# 555.net
KiCad netlist of a schematic drawn in EAGLE
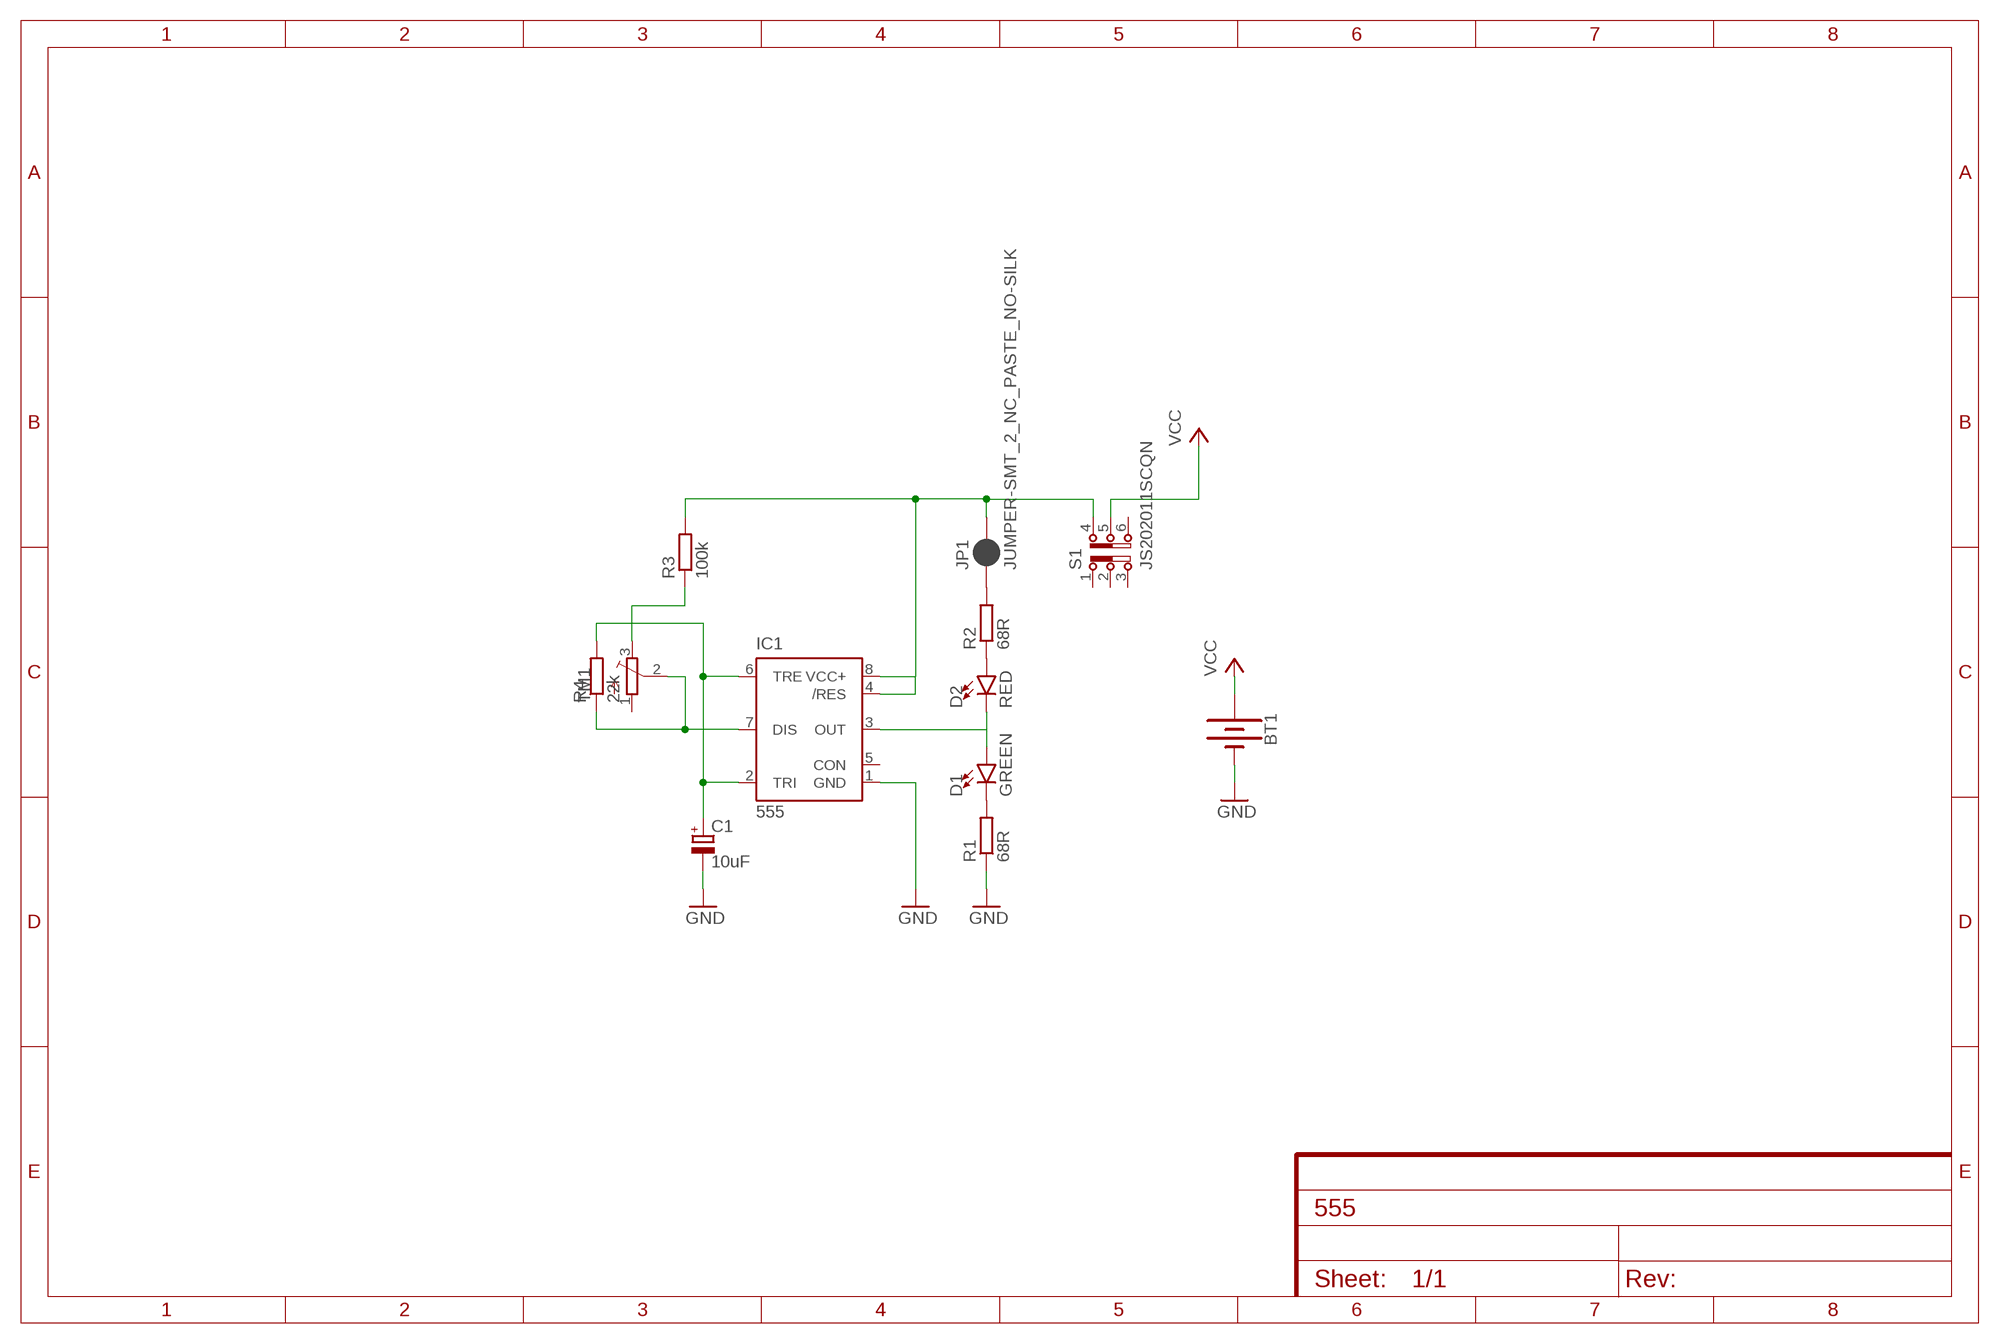
[diagram p0: schematic, sheet 1]

(export (version "E")
  (design (tool "Eeschema 10.0.6"))
  (components
    (comp (ref "BT1")
      (value "BATTERY-20MM_SMD")
      (footprint "eagle-import:BATTCON_20MM")
      (libsource (lib "eagle-import") (part "BATTERY-20MM_SMD"))
    )
    (comp (ref "C1")
      (value "10uF")
      (footprint "eagle-import:SMC_A")
      (libsource (lib "eagle-import") (part "CPOL-EUSMCA"))
    )
    (comp (ref "D1")
      (value "GREEN")
      (footprint "eagle-import:LED-1206")
      (libsource (lib "eagle-import") (part "LED-GREEN1206"))
    )
    (comp (ref "D2")
      (value "RED")
      (footprint "eagle-import:LED-1206")
      (libsource (lib "eagle-import") (part "LED1206"))
    )
    (comp (ref "IC1")
      (value "555")
      (footprint "eagle-import:SO08")
      (libsource (lib "eagle-import") (part "555D"))
    )
    (comp (ref "JP1")
      (value "JUMPER-SMT_2_NC_PASTE_NO-SILK")
      (footprint "eagle-import:SMT-JUMPER_2_NC_PASTE_NO-SILK")
      (libsource (lib "eagle-import") (part "JUMPER-SMT_2_NC_PASTE_NO-SILK"))
    )
    (comp (ref "R1")
      (value "68R")
      (footprint "eagle-import:R0603")
      (libsource (lib "eagle-import") (part "R-EU_R0603"))
    )
    (comp (ref "R2")
      (value "68R")
      (footprint "eagle-import:R0603")
      (libsource (lib "eagle-import") (part "R-EU_R0603"))
    )
    (comp (ref "R3")
      (value "100k")
      (footprint "eagle-import:R0603")
      (libsource (lib "eagle-import") (part "R-EU_R0603"))
    )
    (comp (ref "R4")
      (value "22k")
      (footprint "eagle-import:R0603")
      (libsource (lib "eagle-import") (part "R-EU_R0603"))
    )
    (comp (ref "S1")
      (value "JS202011SCQN")
      (footprint "eagle-import:JS202011SCQN")
      (libsource (lib "eagle-import") (part "JS202011SCQN"))
    )
    (comp (ref "TM1")
      (value "TRIMPOTTC33X")
      (footprint "eagle-import:TC33X")
      (libsource (lib "eagle-import") (part "TRIMPOTTC33X"))
    )
  )
  (nets
    (net (code "1") (name "GND") (class "Default")
      (node (ref "BT1") (pin "2") (pinfunction "-_2") (pintype "power_in"))
      (node (ref "C1") (pin "-") (pinfunction "-_-") (pintype "passive"))
      (node (ref "IC1") (pin "1") (pinfunction "GND_1") (pintype "power_in"))
      (node (ref "R1") (pin "1") (pinfunction "1_1") (pintype "passive"))
    )
    (net (code "2") (name "Net-(D1-PadC)") (class "Default")
      (node (ref "D1") (pin "C") (pinfunction "C_C") (pintype "passive"))
      (node (ref "R1") (pin "2") (pinfunction "2_2") (pintype "passive"))
    )
    (net (code "3") (name "Net-(D2-PadA)") (class "Default")
      (node (ref "D2") (pin "A") (pinfunction "A_A") (pintype "passive"))
      (node (ref "R2") (pin "1") (pinfunction "1_1") (pintype "passive"))
    )
    (net (code "4") (name "Net-(IC1-DIS)") (class "Default")
      (node (ref "IC1") (pin "7") (pinfunction "DIS_7") (pintype "input"))
      (node (ref "R4") (pin "1") (pinfunction "1_1") (pintype "passive"))
      (node (ref "TM1") (pin "2") (pinfunction "S_2") (pintype "passive"))
    )
    (net (code "5") (name "Net-(IC1-OUT)") (class "Default")
      (node (ref "D1") (pin "A") (pinfunction "A_A") (pintype "passive"))
      (node (ref "D2") (pin "C") (pinfunction "C_C") (pintype "passive"))
      (node (ref "IC1") (pin "3") (pinfunction "OUT_3") (pintype "output"))
    )
    (net (code "6") (name "Net-(IC1-TRE)") (class "Default")
      (node (ref "C1") (pin "+") (pinfunction "+_+") (pintype "passive"))
      (node (ref "IC1") (pin "2") (pinfunction "TRI_2") (pintype "input"))
      (node (ref "IC1") (pin "6") (pinfunction "TRE_6") (pintype "input"))
      (node (ref "R4") (pin "2") (pinfunction "2_2") (pintype "passive"))
    )
    (net (code "7") (name "Net-(IC1-VCC+)") (class "Default")
      (node (ref "IC1") (pin "4") (pinfunction "/RES_4") (pintype "input"))
      (node (ref "IC1") (pin "8") (pinfunction "VCC+_8") (pintype "power_in"))
      (node (ref "JP1") (pin "2") (pinfunction "2_2") (pintype "passive"))
      (node (ref "R3") (pin "2") (pinfunction "2_2") (pintype "passive"))
      (node (ref "S1") (pin "4") (pinfunction "4_4") (pintype "passive"))
    )
    (net (code "8") (name "Net-(JP1-Pad1)") (class "Default")
      (node (ref "JP1") (pin "1") (pinfunction "1_1") (pintype "passive"))
      (node (ref "R2") (pin "2") (pinfunction "2_2") (pintype "passive"))
    )
    (net (code "9") (name "Net-(TM1-E)") (class "Default")
      (node (ref "R3") (pin "1") (pinfunction "1_1") (pintype "passive"))
      (node (ref "TM1") (pin "3") (pinfunction "E_3") (pintype "passive"))
    )
    (net (code "10") (name "VCC") (class "Default")
      (node (ref "BT1") (pin "1") (pinfunction "+_1") (pintype "power_in"))
      (node (ref "S1") (pin "5") (pinfunction "5_5") (pintype "passive"))
    )
    (net (code "11") (name "unconnected-(IC1-CON-Pad5)") (class "Default")
      (node (ref "IC1") (pin "5") (pinfunction "CON_5") (pintype "input"))
    )
    (net (code "12") (name "unconnected-(S1-Pad1)") (class "Default")
      (node (ref "S1") (pin "1") (pinfunction "1_1") (pintype "passive"))
    )
    (net (code "13") (name "unconnected-(S1-Pad2)") (class "Default")
      (node (ref "S1") (pin "2") (pinfunction "2_2") (pintype "passive"))
    )
    (net (code "14") (name "unconnected-(S1-Pad3)") (class "Default")
      (node (ref "S1") (pin "3") (pinfunction "3_3") (pintype "passive"))
    )
    (net (code "15") (name "unconnected-(S1-Pad6)") (class "Default")
      (node (ref "S1") (pin "6") (pinfunction "6_6") (pintype "passive"))
    )
    (net (code "16") (name "unconnected-(TM1-A-Pad1)") (class "Default")
      (node (ref "TM1") (pin "1") (pinfunction "A_1") (pintype "passive"))
    )
  )
)
